# motor_driver_ver4_0.net
KiCad netlist of a schematic drawn in EAGLE
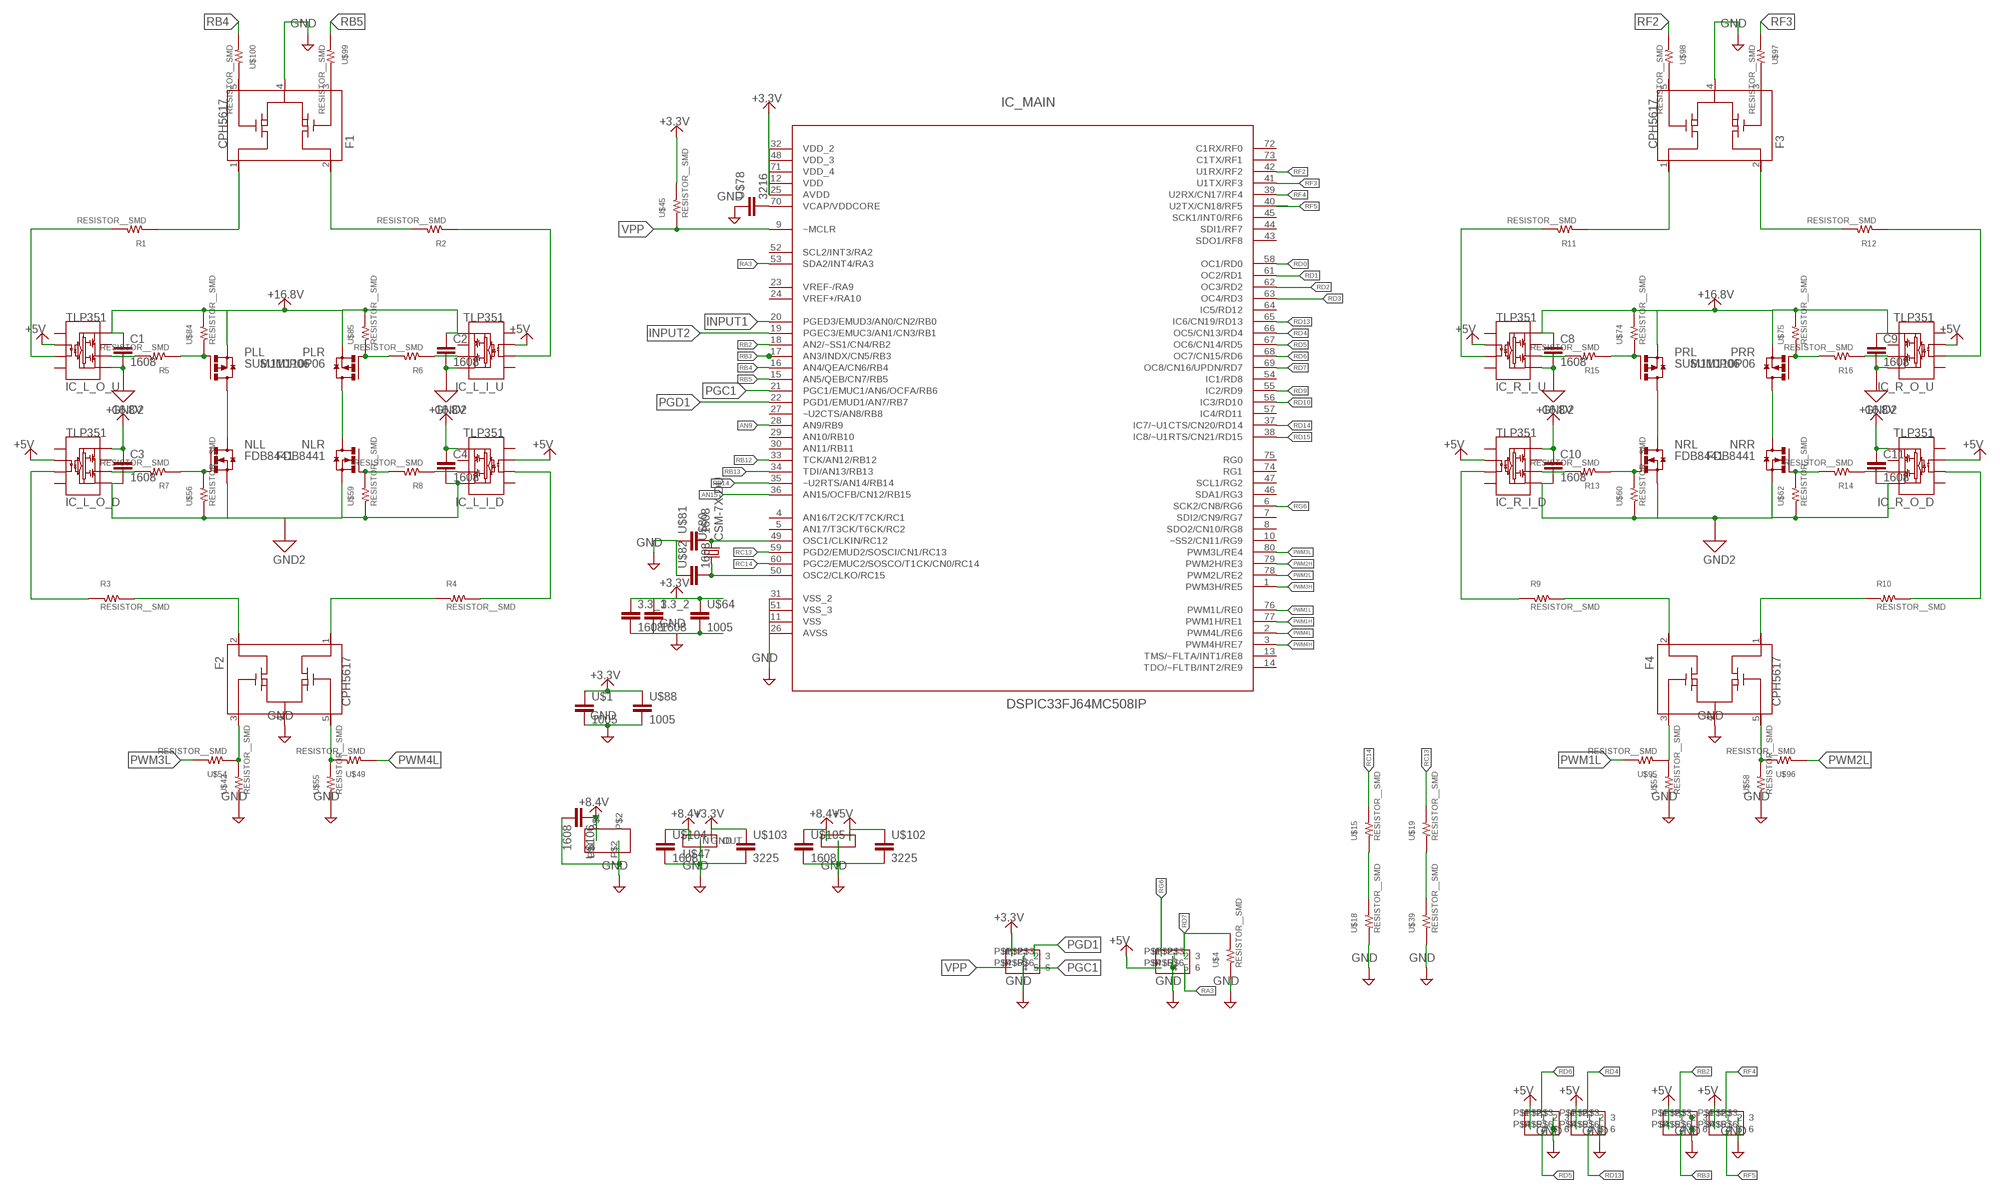
[diagram p0: schematic, sheet 1]

(export (version "E")
  (design (tool "Eeschema 10.0.6"))
  (components
    (comp (ref "3.3_1")
      (value "1608")
      (footprint "eagle-import:1608")
      (libsource (lib "eagle-import") (part "1608"))
    )
    (comp (ref "3.3_2")
      (value "1608")
      (footprint "eagle-import:1608")
      (libsource (lib "eagle-import") (part "1608"))
    )
    (comp (ref "C1")
      (value "1608")
      (footprint "eagle-import:1608")
      (libsource (lib "eagle-import") (part "1608"))
    )
    (comp (ref "C2")
      (value "1608")
      (footprint "eagle-import:1608")
      (libsource (lib "eagle-import") (part "1608"))
    )
    (comp (ref "C3")
      (value "1608")
      (footprint "eagle-import:1608")
      (libsource (lib "eagle-import") (part "1608"))
    )
    (comp (ref "C4")
      (value "1608")
      (footprint "eagle-import:1608")
      (libsource (lib "eagle-import") (part "1608"))
    )
    (comp (ref "C8")
      (value "1608")
      (footprint "eagle-import:1608")
      (libsource (lib "eagle-import") (part "1608"))
    )
    (comp (ref "C9")
      (value "1608")
      (footprint "eagle-import:1608")
      (libsource (lib "eagle-import") (part "1608"))
    )
    (comp (ref "C10")
      (value "1608")
      (footprint "eagle-import:1608")
      (libsource (lib "eagle-import") (part "1608"))
    )
    (comp (ref "C11")
      (value "1608")
      (footprint "eagle-import:1608")
      (libsource (lib "eagle-import") (part "1608"))
    )
    (comp (ref "F1")
      (value "CPH5617")
      (footprint "eagle-import:CHP-5")
      (libsource (lib "eagle-import") (part "CPH5617"))
    )
    (comp (ref "F2")
      (value "CPH5617")
      (footprint "eagle-import:CHP-5")
      (libsource (lib "eagle-import") (part "CPH5617"))
    )
    (comp (ref "F3")
      (value "CPH5617")
      (footprint "eagle-import:CHP-5")
      (libsource (lib "eagle-import") (part "CPH5617"))
    )
    (comp (ref "F4")
      (value "CPH5617")
      (footprint "eagle-import:CHP-5")
      (libsource (lib "eagle-import") (part "CPH5617"))
    )
    (comp (ref "IC_L_I_D")
      (value "TLP351")
      (footprint "eagle-import:DIL08")
      (libsource (lib "eagle-import") (part "TLP351"))
    )
    (comp (ref "IC_L_I_U")
      (value "TLP351")
      (footprint "eagle-import:DIL08")
      (libsource (lib "eagle-import") (part "TLP351"))
    )
    (comp (ref "IC_L_O_D")
      (value "TLP351")
      (footprint "eagle-import:DIL08")
      (libsource (lib "eagle-import") (part "TLP351"))
    )
    (comp (ref "IC_L_O_U")
      (value "TLP351")
      (footprint "eagle-import:DIL08")
      (libsource (lib "eagle-import") (part "TLP351"))
    )
    (comp (ref "IC_MAIN")
      (value "DSPIC33FJ64MC508IP")
      (footprint "eagle-import:QFP50P1400X1400X120-80N")
      (libsource (lib "eagle-import") (part "DSPIC33FJ64MC508IP"))
    )
    (comp (ref "IC_R_I_D")
      (value "TLP351")
      (footprint "eagle-import:DIL08")
      (libsource (lib "eagle-import") (part "TLP351"))
    )
    (comp (ref "IC_R_I_U")
      (value "TLP351")
      (footprint "eagle-import:DIL08")
      (libsource (lib "eagle-import") (part "TLP351"))
    )
    (comp (ref "IC_R_O_D")
      (value "TLP351")
      (footprint "eagle-import:DIL08")
      (libsource (lib "eagle-import") (part "TLP351"))
    )
    (comp (ref "IC_R_O_U")
      (value "TLP351")
      (footprint "eagle-import:DIL08")
      (libsource (lib "eagle-import") (part "TLP351"))
    )
    (comp (ref "NLL")
      (value "FDB8441")
      (footprint "eagle-import:TO-263")
      (libsource (lib "eagle-import") (part "FDB8441"))
    )
    (comp (ref "NLR")
      (value "FDB8441")
      (footprint "eagle-import:TO-263")
      (libsource (lib "eagle-import") (part "FDB8441"))
    )
    (comp (ref "NRL")
      (value "FDB8441")
      (footprint "eagle-import:TO-263")
      (libsource (lib "eagle-import") (part "FDB8441"))
    )
    (comp (ref "NRR")
      (value "FDB8441")
      (footprint "eagle-import:TO-263")
      (libsource (lib "eagle-import") (part "FDB8441"))
    )
    (comp (ref "PLL")
      (value "SUM110P06")
      (footprint "eagle-import:TO-263")
      (libsource (lib "eagle-import") (part "SUM110P06"))
    )
    (comp (ref "PLR")
      (value "SUM110P06")
      (footprint "eagle-import:TO-263")
      (libsource (lib "eagle-import") (part "SUM110P06"))
    )
    (comp (ref "PRL")
      (value "SUM110P06")
      (footprint "eagle-import:TO-263")
      (libsource (lib "eagle-import") (part "SUM110P06"))
    )
    (comp (ref "PRR")
      (value "SUM110P06")
      (footprint "eagle-import:TO-263")
      (libsource (lib "eagle-import") (part "SUM110P06"))
    )
    (comp (ref "R1")
      (value "RESISTOR__SMD")
      (footprint "eagle-import:1608")
      (libsource (lib "eagle-import") (part "RESISTOR__SMD"))
    )
    (comp (ref "R2")
      (value "RESISTOR__SMD")
      (footprint "eagle-import:1608")
      (libsource (lib "eagle-import") (part "RESISTOR__SMD"))
    )
    (comp (ref "R3")
      (value "RESISTOR__SMD")
      (footprint "eagle-import:1608")
      (libsource (lib "eagle-import") (part "RESISTOR__SMD"))
    )
    (comp (ref "R4")
      (value "RESISTOR__SMD")
      (footprint "eagle-import:1608")
      (libsource (lib "eagle-import") (part "RESISTOR__SMD"))
    )
    (comp (ref "R5")
      (value "RESISTOR__SMD")
      (footprint "eagle-import:1608")
      (libsource (lib "eagle-import") (part "RESISTOR__SMD"))
    )
    (comp (ref "R6")
      (value "RESISTOR__SMD")
      (footprint "eagle-import:1608")
      (libsource (lib "eagle-import") (part "RESISTOR__SMD"))
    )
    (comp (ref "R7")
      (value "RESISTOR__SMD")
      (footprint "eagle-import:1608")
      (libsource (lib "eagle-import") (part "RESISTOR__SMD"))
    )
    (comp (ref "R8")
      (value "RESISTOR__SMD")
      (footprint "eagle-import:1608")
      (libsource (lib "eagle-import") (part "RESISTOR__SMD"))
    )
    (comp (ref "R9")
      (value "RESISTOR__SMD")
      (footprint "eagle-import:1608")
      (libsource (lib "eagle-import") (part "RESISTOR__SMD"))
    )
    (comp (ref "R10")
      (value "RESISTOR__SMD")
      (footprint "eagle-import:1608")
      (libsource (lib "eagle-import") (part "RESISTOR__SMD"))
    )
    (comp (ref "R11")
      (value "RESISTOR__SMD")
      (footprint "eagle-import:1608")
      (libsource (lib "eagle-import") (part "RESISTOR__SMD"))
    )
    (comp (ref "R12")
      (value "RESISTOR__SMD")
      (footprint "eagle-import:1608")
      (libsource (lib "eagle-import") (part "RESISTOR__SMD"))
    )
    (comp (ref "R13")
      (value "RESISTOR__SMD")
      (footprint "eagle-import:1608")
      (libsource (lib "eagle-import") (part "RESISTOR__SMD"))
    )
    (comp (ref "R14")
      (value "RESISTOR__SMD")
      (footprint "eagle-import:1608")
      (libsource (lib "eagle-import") (part "RESISTOR__SMD"))
    )
    (comp (ref "R15")
      (value "RESISTOR__SMD")
      (footprint "eagle-import:1608")
      (libsource (lib "eagle-import") (part "RESISTOR__SMD"))
    )
    (comp (ref "R16")
      (value "RESISTOR__SMD")
      (footprint "eagle-import:1608")
      (libsource (lib "eagle-import") (part "RESISTOR__SMD"))
    )
    (comp (ref "RA3")
      (value "PIN_HEADER_32")
      (footprint "eagle-import:PIN_HEADER_3_2")
      (libsource (lib "eagle-import") (part "PIN_HEADER_32"))
    )
    (comp (ref "U$1")
      (value "1005")
      (footprint "eagle-import:1005")
      (libsource (lib "eagle-import") (part "1005"))
    )
    (comp (ref "U$4")
      (value "RESISTOR__SMD")
      (footprint "eagle-import:1608")
      (libsource (lib "eagle-import") (part "RESISTOR__SMD"))
    )
    (comp (ref "U$5")
      (value "PIN_HEADER_32")
      (footprint "eagle-import:PIN_HEADER_3_2")
      (libsource (lib "eagle-import") (part "PIN_HEADER_32"))
    )
    (comp (ref "U$15")
      (value "RESISTOR__SMD")
      (footprint "eagle-import:1608")
      (libsource (lib "eagle-import") (part "RESISTOR__SMD"))
    )
    (comp (ref "U$18")
      (value "RESISTOR__SMD")
      (footprint "eagle-import:1608")
      (libsource (lib "eagle-import") (part "RESISTOR__SMD"))
    )
    (comp (ref "U$19")
      (value "RESISTOR__SMD")
      (footprint "eagle-import:1608")
      (libsource (lib "eagle-import") (part "RESISTOR__SMD"))
    )
    (comp (ref "U$20")
      (value "PIN_HEADER_32")
      (footprint "eagle-import:PIN_HEADER_3_2")
      (libsource (lib "eagle-import") (part "PIN_HEADER_32"))
    )
    (comp (ref "U$39")
      (value "RESISTOR__SMD")
      (footprint "eagle-import:1608")
      (libsource (lib "eagle-import") (part "RESISTOR__SMD"))
    )
    (comp (ref "U$42")
      (value "RESISTOR__SMD")
      (footprint "eagle-import:1608")
      (libsource (lib "eagle-import") (part "RESISTOR__SMD"))
    )
    (comp (ref "U$45")
      (value "RESISTOR__SMD")
      (footprint "eagle-import:1608")
      (libsource (lib "eagle-import") (part "RESISTOR__SMD"))
    )
    (comp (ref "U$47")
      (value "TA48M033F")
      (footprint "eagle-import:ＴＡ４８")
      (libsource (lib "eagle-import") (part "TA48M033F"))
    )
    (comp (ref "U$49")
      (value "RESISTOR__SMD")
      (footprint "eagle-import:1608")
      (libsource (lib "eagle-import") (part "RESISTOR__SMD"))
    )
    (comp (ref "U$51")
      (value "PIN_HEADER_2")
      (footprint "eagle-import:PIN_HEADER_2S")
      (libsource (lib "eagle-import") (part "PIN_HEADER_2"))
    )
    (comp (ref "U$54")
      (value "RESISTOR__SMD")
      (footprint "eagle-import:1608")
      (libsource (lib "eagle-import") (part "RESISTOR__SMD"))
    )
    (comp (ref "U$55")
      (value "RESISTOR__SMD")
      (footprint "eagle-import:1608")
      (libsource (lib "eagle-import") (part "RESISTOR__SMD"))
    )
    (comp (ref "U$56")
      (value "RESISTOR__SMD")
      (footprint "eagle-import:1608")
      (libsource (lib "eagle-import") (part "RESISTOR__SMD"))
    )
    (comp (ref "U$57")
      (value "RESISTOR__SMD")
      (footprint "eagle-import:1608")
      (libsource (lib "eagle-import") (part "RESISTOR__SMD"))
    )
    (comp (ref "U$58")
      (value "RESISTOR__SMD")
      (footprint "eagle-import:1608")
      (libsource (lib "eagle-import") (part "RESISTOR__SMD"))
    )
    (comp (ref "U$59")
      (value "RESISTOR__SMD")
      (footprint "eagle-import:1608")
      (libsource (lib "eagle-import") (part "RESISTOR__SMD"))
    )
    (comp (ref "U$60")
      (value "RESISTOR__SMD")
      (footprint "eagle-import:1608")
      (libsource (lib "eagle-import") (part "RESISTOR__SMD"))
    )
    (comp (ref "U$62")
      (value "RESISTOR__SMD")
      (footprint "eagle-import:1608")
      (libsource (lib "eagle-import") (part "RESISTOR__SMD"))
    )
    (comp (ref "U$64")
      (value "1005")
      (footprint "eagle-import:1005")
      (libsource (lib "eagle-import") (part "1005"))
    )
    (comp (ref "U$65")
      (value "TA48M05F")
      (footprint "eagle-import:ＴＡ４８")
      (libsource (lib "eagle-import") (part "TA48M05F"))
    )
    (comp (ref "U$66")
      (value "PIN_HEADER_32")
      (footprint "eagle-import:PIN_HEADER_3_2")
      (libsource (lib "eagle-import") (part "PIN_HEADER_32"))
    )
    (comp (ref "U$67")
      (value "PIN_HEADER_32")
      (footprint "eagle-import:PIN_HEADER_3_2")
      (libsource (lib "eagle-import") (part "PIN_HEADER_32"))
    )
    (comp (ref "U$74")
      (value "RESISTOR__SMD")
      (footprint "eagle-import:1608")
      (libsource (lib "eagle-import") (part "RESISTOR__SMD"))
    )
    (comp (ref "U$75")
      (value "RESISTOR__SMD")
      (footprint "eagle-import:1608")
      (libsource (lib "eagle-import") (part "RESISTOR__SMD"))
    )
    (comp (ref "U$78")
      (value "3216")
      (footprint "eagle-import:3216")
      (libsource (lib "eagle-import") (part "3216"))
    )
    (comp (ref "U$80")
      (value "CSM-7X-DU")
      (footprint "eagle-import:CSM-7X-DU")
      (libsource (lib "eagle-import") (part "CSM-7X-DU"))
    )
    (comp (ref "U$81")
      (value "1608")
      (footprint "eagle-import:1608")
      (libsource (lib "eagle-import") (part "1608"))
    )
    (comp (ref "U$82")
      (value "1608")
      (footprint "eagle-import:1608")
      (libsource (lib "eagle-import") (part "1608"))
    )
    (comp (ref "U$84")
      (value "RESISTOR__SMD")
      (footprint "eagle-import:1608")
      (libsource (lib "eagle-import") (part "RESISTOR__SMD"))
    )
    (comp (ref "U$85")
      (value "RESISTOR__SMD")
      (footprint "eagle-import:1608")
      (libsource (lib "eagle-import") (part "RESISTOR__SMD"))
    )
    (comp (ref "U$86")
      (value "PIN_HEADER_32")
      (footprint "eagle-import:PIN_HEADER_3_2")
      (libsource (lib "eagle-import") (part "PIN_HEADER_32"))
    )
    (comp (ref "U$88")
      (value "1005")
      (footprint "eagle-import:1005")
      (libsource (lib "eagle-import") (part "1005"))
    )
    (comp (ref "U$95")
      (value "RESISTOR__SMD")
      (footprint "eagle-import:1608")
      (libsource (lib "eagle-import") (part "RESISTOR__SMD"))
    )
    (comp (ref "U$96")
      (value "RESISTOR__SMD")
      (footprint "eagle-import:1608")
      (libsource (lib "eagle-import") (part "RESISTOR__SMD"))
    )
    (comp (ref "U$97")
      (value "RESISTOR__SMD")
      (footprint "eagle-import:1608")
      (libsource (lib "eagle-import") (part "RESISTOR__SMD"))
    )
    (comp (ref "U$98")
      (value "RESISTOR__SMD")
      (footprint "eagle-import:1608")
      (libsource (lib "eagle-import") (part "RESISTOR__SMD"))
    )
    (comp (ref "U$99")
      (value "RESISTOR__SMD")
      (footprint "eagle-import:1608")
      (libsource (lib "eagle-import") (part "RESISTOR__SMD"))
    )
    (comp (ref "U$100")
      (value "RESISTOR__SMD")
      (footprint "eagle-import:1608")
      (libsource (lib "eagle-import") (part "RESISTOR__SMD"))
    )
    (comp (ref "U$102")
      (value "3225")
      (footprint "eagle-import:3225")
      (libsource (lib "eagle-import") (part "3225"))
    )
    (comp (ref "U$103")
      (value "3225")
      (footprint "eagle-import:3225")
      (libsource (lib "eagle-import") (part "3225"))
    )
    (comp (ref "U$104")
      (value "1608")
      (footprint "eagle-import:1608")
      (libsource (lib "eagle-import") (part "1608"))
    )
    (comp (ref "U$105")
      (value "1608")
      (footprint "eagle-import:1608")
      (libsource (lib "eagle-import") (part "1608"))
    )
    (comp (ref "U$106")
      (value "1608")
      (footprint "eagle-import:1608")
      (libsource (lib "eagle-import") (part "1608"))
    )
  )
  (nets
    (net (code "1") (name "+3.3V") (class "Default")
      (node (ref "3.3_1") (pin "P$1") (pinfunction "1_P$1") (pintype "passive"))
      (node (ref "3.3_2") (pin "P$1") (pinfunction "1_P$1") (pintype "passive"))
      (node (ref "IC_MAIN") (pin "12") (pinfunction "VDD_12") (pintype "power_in"))
      (node (ref "IC_MAIN") (pin "25") (pinfunction "AVDD_25") (pintype "power_in"))
      (node (ref "IC_MAIN") (pin "32") (pinfunction "VDD_2_32") (pintype "power_in"))
      (node (ref "IC_MAIN") (pin "48") (pinfunction "VDD_3_48") (pintype "power_in"))
      (node (ref "IC_MAIN") (pin "71") (pinfunction "VDD_4_71") (pintype "power_in"))
      (node (ref "U$1") (pin "1") (pinfunction "1_1") (pintype "passive"))
      (node (ref "U$103") (pin "P$1") (pinfunction "1_P$1") (pintype "passive"))
      (node (ref "U$45") (pin "2") (pinfunction "P$2_2") (pintype "passive"))
      (node (ref "U$47") (pin "3") (pinfunction "OUT_3") (pintype "bidirectional"))
      (node (ref "U$64") (pin "1") (pinfunction "1_1") (pintype "passive"))
      (node (ref "U$86") (pin "P$1") (pinfunction "1_P$1") (pintype "bidirectional"))
      (node (ref "U$88") (pin "1") (pinfunction "1_1") (pintype "passive"))
    )
    (net (code "2") (name "+5V") (class "Default")
      (node (ref "IC_L_I_D") (pin "2") (pinfunction "LED+_2") (pintype "bidirectional"))
      (node (ref "IC_L_I_U") (pin "2") (pinfunction "LED+_2") (pintype "bidirectional"))
      (node (ref "IC_L_O_D") (pin "2") (pinfunction "LED+_2") (pintype "bidirectional"))
      (node (ref "IC_L_O_U") (pin "2") (pinfunction "LED+_2") (pintype "bidirectional"))
      (node (ref "IC_R_I_D") (pin "2") (pinfunction "LED+_2") (pintype "bidirectional"))
      (node (ref "IC_R_I_U") (pin "2") (pinfunction "LED+_2") (pintype "bidirectional"))
      (node (ref "IC_R_O_D") (pin "2") (pinfunction "LED+_2") (pintype "bidirectional"))
      (node (ref "IC_R_O_U") (pin "2") (pinfunction "LED+_2") (pintype "bidirectional"))
      (node (ref "RA3") (pin "P$4") (pinfunction "4_P$4") (pintype "bidirectional"))
      (node (ref "U$102") (pin "P$1") (pinfunction "1_P$1") (pintype "passive"))
      (node (ref "U$20") (pin "P$1") (pinfunction "1_P$1") (pintype "bidirectional"))
      (node (ref "U$20") (pin "P$4") (pinfunction "4_P$4") (pintype "bidirectional"))
      (node (ref "U$5") (pin "P$1") (pinfunction "1_P$1") (pintype "bidirectional"))
      (node (ref "U$5") (pin "P$4") (pinfunction "4_P$4") (pintype "bidirectional"))
      (node (ref "U$65") (pin "3") (pinfunction "OUT_3") (pintype "bidirectional"))
      (node (ref "U$66") (pin "P$1") (pinfunction "1_P$1") (pintype "bidirectional"))
      (node (ref "U$66") (pin "P$4") (pinfunction "4_P$4") (pintype "bidirectional"))
      (node (ref "U$67") (pin "P$1") (pinfunction "1_P$1") (pintype "bidirectional"))
      (node (ref "U$67") (pin "P$4") (pinfunction "4_P$4") (pintype "bidirectional"))
    )
    (net (code "3") (name "+8.4V") (class "Default")
      (node (ref "U$104") (pin "P$1") (pinfunction "1_P$1") (pintype "passive"))
      (node (ref "U$105") (pin "P$1") (pinfunction "1_P$1") (pintype "passive"))
      (node (ref "U$106") (pin "P$1") (pinfunction "1_P$1") (pintype "passive"))
      (node (ref "U$47") (pin "1") (pinfunction "IN_1") (pintype "bidirectional"))
      (node (ref "U$51") (pin "P$1") (pinfunction "P$1_P$1") (pintype "bidirectional"))
      (node (ref "U$65") (pin "1") (pinfunction "IN_1") (pintype "bidirectional"))
    )
    (net (code "4") (name "+16.8V") (class "Default")
      (node (ref "C1") (pin "P$1") (pinfunction "1_P$1") (pintype "passive"))
      (node (ref "C10") (pin "P$1") (pinfunction "1_P$1") (pintype "passive"))
      (node (ref "C11") (pin "P$1") (pinfunction "1_P$1") (pintype "passive"))
      (node (ref "C2") (pin "P$1") (pinfunction "1_P$1") (pintype "passive"))
      (node (ref "C3") (pin "P$1") (pinfunction "1_P$1") (pintype "passive"))
      (node (ref "C4") (pin "P$1") (pinfunction "1_P$1") (pintype "passive"))
      (node (ref "C8") (pin "P$1") (pinfunction "1_P$1") (pintype "passive"))
      (node (ref "C9") (pin "P$1") (pinfunction "1_P$1") (pintype "passive"))
      (node (ref "IC_L_I_D") (pin "8") (pinfunction "VDD_8") (pintype "bidirectional"))
      (node (ref "IC_L_I_U") (pin "8") (pinfunction "VDD_8") (pintype "bidirectional"))
      (node (ref "IC_L_O_D") (pin "8") (pinfunction "VDD_8") (pintype "bidirectional"))
      (node (ref "IC_L_O_U") (pin "8") (pinfunction "VDD_8") (pintype "bidirectional"))
      (node (ref "IC_R_I_D") (pin "8") (pinfunction "VDD_8") (pintype "bidirectional"))
      (node (ref "IC_R_I_U") (pin "8") (pinfunction "VDD_8") (pintype "bidirectional"))
      (node (ref "IC_R_O_D") (pin "8") (pinfunction "VDD_8") (pintype "bidirectional"))
      (node (ref "IC_R_O_U") (pin "8") (pinfunction "VDD_8") (pintype "bidirectional"))
      (node (ref "PLL") (pin "2") (pinfunction "S_2") (pintype "passive"))
      (node (ref "PLR") (pin "2") (pinfunction "S_2") (pintype "passive"))
      (node (ref "PRL") (pin "2") (pinfunction "S_2") (pintype "passive"))
      (node (ref "PRR") (pin "2") (pinfunction "S_2") (pintype "passive"))
      (node (ref "U$74") (pin "2") (pinfunction "P$2_2") (pintype "passive"))
      (node (ref "U$75") (pin "2") (pinfunction "P$2_2") (pintype "passive"))
      (node (ref "U$84") (pin "2") (pinfunction "P$2_2") (pintype "passive"))
      (node (ref "U$85") (pin "2") (pinfunction "P$2_2") (pintype "passive"))
    )
    (net (code "5") (name "AN9") (class "Default")
      (node (ref "IC_MAIN") (pin "28") (pinfunction "AN9/RB9_28") (pintype "bidirectional"))
    )
    (net (code "6") (name "AN15") (class "Default")
      (node (ref "IC_MAIN") (pin "36") (pinfunction "AN15/OCFB/CN12/RB15_36") (pintype "bidirectional"))
    )
    (net (code "7") (name "GND") (class "Default")
      (node (ref "3.3_1") (pin "P$2") (pinfunction "2_P$2") (pintype "passive"))
      (node (ref "3.3_2") (pin "P$2") (pinfunction "2_P$2") (pintype "passive"))
      (node (ref "F1") (pin "4") (pinfunction "S_4") (pintype "bidirectional"))
      (node (ref "F2") (pin "4") (pinfunction "S_4") (pintype "bidirectional"))
      (node (ref "F3") (pin "4") (pinfunction "S_4") (pintype "bidirectional"))
      (node (ref "F4") (pin "4") (pinfunction "S_4") (pintype "bidirectional"))
      (node (ref "IC_MAIN") (pin "11") (pinfunction "VSS_11") (pintype "power_in"))
      (node (ref "IC_MAIN") (pin "26") (pinfunction "AVSS_26") (pintype "power_in"))
      (node (ref "IC_MAIN") (pin "31") (pinfunction "VSS_2_31") (pintype "power_in"))
      (node (ref "IC_MAIN") (pin "51") (pinfunction "VSS_3_51") (pintype "power_in"))
      (node (ref "RA3") (pin "P$2") (pinfunction "2_P$2") (pintype "bidirectional"))
      (node (ref "RA3") (pin "P$5") (pinfunction "5_P$5") (pintype "bidirectional"))
      (node (ref "U$1") (pin "2") (pinfunction "2_2") (pintype "passive"))
      (node (ref "U$102") (pin "P$2") (pinfunction "2_P$2") (pintype "passive"))
      (node (ref "U$103") (pin "P$2") (pinfunction "2_P$2") (pintype "passive"))
      (node (ref "U$104") (pin "P$2") (pinfunction "2_P$2") (pintype "passive"))
      (node (ref "U$105") (pin "P$2") (pinfunction "2_P$2") (pintype "passive"))
      (node (ref "U$106") (pin "P$2") (pinfunction "2_P$2") (pintype "passive"))
      (node (ref "U$18") (pin "1") (pinfunction "P$1_1") (pintype "passive"))
      (node (ref "U$20") (pin "P$3") (pinfunction "3_P$3") (pintype "bidirectional"))
      (node (ref "U$20") (pin "P$6") (pinfunction "6_P$6") (pintype "bidirectional"))
      (node (ref "U$39") (pin "1") (pinfunction "P$1_1") (pintype "passive"))
      (node (ref "U$4") (pin "1") (pinfunction "P$1_1") (pintype "passive"))
      (node (ref "U$42") (pin "1") (pinfunction "P$1_1") (pintype "passive"))
      (node (ref "U$47") (pin "2") (pinfunction "GND_2") (pintype "bidirectional"))
      (node (ref "U$5") (pin "P$3") (pinfunction "3_P$3") (pintype "bidirectional"))
      (node (ref "U$5") (pin "P$6") (pinfunction "6_P$6") (pintype "bidirectional"))
      (node (ref "U$51") (pin "P$2") (pinfunction "P$2_P$2") (pintype "bidirectional"))
      (node (ref "U$55") (pin "1") (pinfunction "P$1_1") (pintype "passive"))
      (node (ref "U$57") (pin "1") (pinfunction "P$1_1") (pintype "passive"))
      (node (ref "U$58") (pin "1") (pinfunction "P$1_1") (pintype "passive"))
      (node (ref "U$64") (pin "2") (pinfunction "2_2") (pintype "passive"))
      (node (ref "U$65") (pin "2") (pinfunction "GND_2") (pintype "bidirectional"))
      (node (ref "U$66") (pin "P$3") (pinfunction "3_P$3") (pintype "bidirectional"))
      (node (ref "U$66") (pin "P$6") (pinfunction "6_P$6") (pintype "bidirectional"))
      (node (ref "U$67") (pin "P$3") (pinfunction "3_P$3") (pintype "bidirectional"))
      (node (ref "U$67") (pin "P$6") (pinfunction "6_P$6") (pintype "bidirectional"))
      (node (ref "U$78") (pin "P$1") (pinfunction "1_P$1") (pintype "passive"))
      (node (ref "U$81") (pin "P$1") (pinfunction "1_P$1") (pintype "passive"))
      (node (ref "U$82") (pin "P$1") (pinfunction "1_P$1") (pintype "passive"))
      (node (ref "U$86") (pin "P$2") (pinfunction "2_P$2") (pintype "bidirectional"))
      (node (ref "U$86") (pin "P$5") (pinfunction "5_P$5") (pintype "bidirectional"))
      (node (ref "U$88") (pin "2") (pinfunction "2_2") (pintype "passive"))
    )
    (net (code "8") (name "GND2") (class "Default")
      (node (ref "C1") (pin "P$2") (pinfunction "2_P$2") (pintype "passive"))
      (node (ref "C10") (pin "P$2") (pinfunction "2_P$2") (pintype "passive"))
      (node (ref "C11") (pin "P$2") (pinfunction "2_P$2") (pintype "passive"))
      (node (ref "C2") (pin "P$2") (pinfunction "2_P$2") (pintype "passive"))
      (node (ref "C3") (pin "P$2") (pinfunction "2_P$2") (pintype "passive"))
      (node (ref "C4") (pin "P$2") (pinfunction "2_P$2") (pintype "passive"))
      (node (ref "C8") (pin "P$2") (pinfunction "2_P$2") (pintype "passive"))
      (node (ref "C9") (pin "P$2") (pinfunction "2_P$2") (pintype "passive"))
      (node (ref "IC_L_I_D") (pin "5") (pinfunction "GND_5") (pintype "bidirectional"))
      (node (ref "IC_L_I_U") (pin "5") (pinfunction "GND_5") (pintype "bidirectional"))
      (node (ref "IC_L_O_D") (pin "5") (pinfunction "GND_5") (pintype "bidirectional"))
      (node (ref "IC_L_O_U") (pin "5") (pinfunction "GND_5") (pintype "bidirectional"))
      (node (ref "IC_R_I_D") (pin "5") (pinfunction "GND_5") (pintype "bidirectional"))
      (node (ref "IC_R_I_U") (pin "5") (pinfunction "GND_5") (pintype "bidirectional"))
      (node (ref "IC_R_O_D") (pin "5") (pinfunction "GND_5") (pintype "bidirectional"))
      (node (ref "IC_R_O_U") (pin "5") (pinfunction "GND_5") (pintype "bidirectional"))
      (node (ref "NLL") (pin "2") (pinfunction "S_2") (pintype "passive"))
      (node (ref "NLR") (pin "2") (pinfunction "S_2") (pintype "passive"))
      (node (ref "NRL") (pin "2") (pinfunction "S_2") (pintype "passive"))
      (node (ref "NRR") (pin "2") (pinfunction "S_2") (pintype "passive"))
      (node (ref "U$56") (pin "1") (pinfunction "P$1_1") (pintype "passive"))
      (node (ref "U$59") (pin "1") (pinfunction "P$1_1") (pintype "passive"))
      (node (ref "U$60") (pin "1") (pinfunction "P$1_1") (pintype "passive"))
      (node (ref "U$62") (pin "1") (pinfunction "P$1_1") (pintype "passive"))
    )
    (net (code "9") (name "INPUT1") (class "Default")
      (node (ref "IC_MAIN") (pin "20") (pinfunction "PGED3/EMUD3/AN0/CN2/RB0_20") (pintype "bidirectional"))
    )
    (net (code "10") (name "INPUT2") (class "Default")
      (node (ref "IC_MAIN") (pin "19") (pinfunction "PGEC3/EMUC3/AN1/CN3/RB1_19") (pintype "bidirectional"))
    )
    (net (code "11") (name "Net-(F1-D1)") (class "Default")
      (node (ref "F1") (pin "1") (pinfunction "D1_1") (pintype "bidirectional"))
      (node (ref "R1") (pin "1") (pinfunction "P$1_1") (pintype "passive"))
    )
    (net (code "12") (name "Net-(F1-D2)") (class "Default")
      (node (ref "F1") (pin "2") (pinfunction "D2_2") (pintype "bidirectional"))
      (node (ref "R2") (pin "2") (pinfunction "P$2_2") (pintype "passive"))
    )
    (net (code "13") (name "Net-(F1-G1)") (class "Default")
      (node (ref "F1") (pin "5") (pinfunction "G1_5") (pintype "bidirectional"))
      (node (ref "U$100") (pin "2") (pinfunction "P$2_2") (pintype "passive"))
    )
    (net (code "14") (name "Net-(F1-G2)") (class "Default")
      (node (ref "F1") (pin "3") (pinfunction "G2_3") (pintype "bidirectional"))
      (node (ref "U$99") (pin "2") (pinfunction "P$2_2") (pintype "passive"))
    )
    (net (code "15") (name "Net-(F2-D1)") (class "Default")
      (node (ref "F2") (pin "1") (pinfunction "D1_1") (pintype "bidirectional"))
      (node (ref "R4") (pin "1") (pinfunction "P$1_1") (pintype "passive"))
    )
    (net (code "16") (name "Net-(F2-D2)") (class "Default")
      (node (ref "F2") (pin "2") (pinfunction "D2_2") (pintype "bidirectional"))
      (node (ref "R3") (pin "2") (pinfunction "P$2_2") (pintype "passive"))
    )
    (net (code "17") (name "Net-(F2-G1)") (class "Default")
      (node (ref "F2") (pin "5") (pinfunction "G1_5") (pintype "bidirectional"))
      (node (ref "U$49") (pin "2") (pinfunction "P$2_2") (pintype "passive"))
      (node (ref "U$55") (pin "2") (pinfunction "P$2_2") (pintype "passive"))
    )
    (net (code "18") (name "Net-(F2-G2)") (class "Default")
      (node (ref "F2") (pin "3") (pinfunction "G2_3") (pintype "bidirectional"))
      (node (ref "U$42") (pin "2") (pinfunction "P$2_2") (pintype "passive"))
      (node (ref "U$54") (pin "1") (pinfunction "P$1_1") (pintype "passive"))
    )
    (net (code "19") (name "Net-(F3-D1)") (class "Default")
      (node (ref "F3") (pin "1") (pinfunction "D1_1") (pintype "bidirectional"))
      (node (ref "R11") (pin "1") (pinfunction "P$1_1") (pintype "passive"))
    )
    (net (code "20") (name "Net-(F3-D2)") (class "Default")
      (node (ref "F3") (pin "2") (pinfunction "D2_2") (pintype "bidirectional"))
      (node (ref "R12") (pin "2") (pinfunction "P$2_2") (pintype "passive"))
    )
    (net (code "21") (name "Net-(F3-G1)") (class "Default")
      (node (ref "F3") (pin "5") (pinfunction "G1_5") (pintype "bidirectional"))
      (node (ref "U$98") (pin "2") (pinfunction "P$2_2") (pintype "passive"))
    )
    (net (code "22") (name "Net-(F3-G2)") (class "Default")
      (node (ref "F3") (pin "3") (pinfunction "G2_3") (pintype "bidirectional"))
      (node (ref "U$97") (pin "2") (pinfunction "P$2_2") (pintype "passive"))
    )
    (net (code "23") (name "Net-(F4-D1)") (class "Default")
      (node (ref "F4") (pin "1") (pinfunction "D1_1") (pintype "bidirectional"))
      (node (ref "R10") (pin "1") (pinfunction "P$1_1") (pintype "passive"))
    )
    (net (code "24") (name "Net-(F4-D2)") (class "Default")
      (node (ref "F4") (pin "2") (pinfunction "D2_2") (pintype "bidirectional"))
      (node (ref "R9") (pin "2") (pinfunction "P$2_2") (pintype "passive"))
    )
    (net (code "25") (name "Net-(F4-G1)") (class "Default")
      (node (ref "F4") (pin "5") (pinfunction "G1_5") (pintype "bidirectional"))
      (node (ref "U$58") (pin "2") (pinfunction "P$2_2") (pintype "passive"))
      (node (ref "U$96") (pin "2") (pinfunction "P$2_2") (pintype "passive"))
    )
    (net (code "26") (name "Net-(F4-G2)") (class "Default")
      (node (ref "F4") (pin "3") (pinfunction "G2_3") (pintype "bidirectional"))
      (node (ref "U$57") (pin "2") (pinfunction "P$2_2") (pintype "passive"))
      (node (ref "U$95") (pin "1") (pinfunction "P$1_1") (pintype "passive"))
    )
    (net (code "27") (name "Net-(IC_L_I_D-LED-)") (class "Default")
      (node (ref "IC_L_I_D") (pin "3") (pinfunction "LED-_3") (pintype "bidirectional"))
      (node (ref "R4") (pin "2") (pinfunction "P$2_2") (pintype "passive"))
    )
    (net (code "28") (name "Net-(IC_L_I_D-OUT)") (class "Default")
      (node (ref "IC_L_I_D") (pin "6") (pinfunction "OUT_6") (pintype "output"))
      (node (ref "R8") (pin "1") (pinfunction "P$1_1") (pintype "passive"))
    )
    (net (code "29") (name "Net-(IC_L_I_U-LED-)") (class "Default")
      (node (ref "IC_L_I_U") (pin "3") (pinfunction "LED-_3") (pintype "bidirectional"))
      (node (ref "R2") (pin "1") (pinfunction "P$1_1") (pintype "passive"))
    )
    (net (code "30") (name "Net-(IC_L_I_U-OUT)") (class "Default")
      (node (ref "IC_L_I_U") (pin "6") (pinfunction "OUT_6") (pintype "output"))
      (node (ref "R6") (pin "1") (pinfunction "P$1_1") (pintype "passive"))
    )
    (net (code "31") (name "Net-(IC_L_O_D-LED-)") (class "Default")
      (node (ref "IC_L_O_D") (pin "3") (pinfunction "LED-_3") (pintype "bidirectional"))
      (node (ref "R3") (pin "1") (pinfunction "P$1_1") (pintype "passive"))
    )
    (net (code "32") (name "Net-(IC_L_O_D-OUT)") (class "Default")
      (node (ref "IC_L_O_D") (pin "6") (pinfunction "OUT_6") (pintype "output"))
      (node (ref "R7") (pin "2") (pinfunction "P$2_2") (pintype "passive"))
    )
    (net (code "33") (name "Net-(IC_L_O_U-LED-)") (class "Default")
      (node (ref "IC_L_O_U") (pin "3") (pinfunction "LED-_3") (pintype "bidirectional"))
      (node (ref "R1") (pin "2") (pinfunction "P$2_2") (pintype "passive"))
    )
    (net (code "34") (name "Net-(IC_L_O_U-OUT)") (class "Default")
      (node (ref "IC_L_O_U") (pin "6") (pinfunction "OUT_6") (pintype "output"))
      (node (ref "R5") (pin "2") (pinfunction "P$2_2") (pintype "passive"))
    )
    (net (code "35") (name "Net-(IC_MAIN-OSC1{slash}CLKIN{slash}RC12)") (class "Default")
      (node (ref "IC_MAIN") (pin "49") (pinfunction "OSC1/CLKIN/RC12_49") (pintype "bidirectional"))
      (node (ref "U$80") (pin "2") (pinfunction "2_2") (pintype "passive"))
      (node (ref "U$81") (pin "P$2") (pinfunction "2_P$2") (pintype "passive"))
    )
    (net (code "36") (name "Net-(IC_MAIN-OSC2{slash}CLKO{slash}RC15)") (class "Default")
      (node (ref "IC_MAIN") (pin "50") (pinfunction "OSC2/CLKO/RC15_50") (pintype "bidirectional"))
      (node (ref "U$80") (pin "1") (pinfunction "1_1") (pintype "passive"))
      (node (ref "U$82") (pin "P$2") (pinfunction "2_P$2") (pintype "passive"))
    )
    (net (code "37") (name "Net-(IC_MAIN-VCAP{slash}VDDCORE)") (class "Default")
      (node (ref "IC_MAIN") (pin "70") (pinfunction "VCAP/VDDCORE_70") (pintype "power_in"))
      (node (ref "U$78") (pin "P$2") (pinfunction "2_P$2") (pintype "passive"))
    )
    (net (code "38") (name "Net-(IC_R_I_D-LED-)") (class "Default")
      (node (ref "IC_R_I_D") (pin "3") (pinfunction "LED-_3") (pintype "bidirectional"))
      (node (ref "R9") (pin "1") (pinfunction "P$1_1") (pintype "passive"))
    )
    (net (code "39") (name "Net-(IC_R_I_D-OUT)") (class "Default")
      (node (ref "IC_R_I_D") (pin "6") (pinfunction "OUT_6") (pintype "output"))
      (node (ref "R13") (pin "2") (pinfunction "P$2_2") (pintype "passive"))
    )
    (net (code "40") (name "Net-(IC_R_I_U-LED-)") (class "Default")
      (node (ref "IC_R_I_U") (pin "3") (pinfunction "LED-_3") (pintype "bidirectional"))
      (node (ref "R11") (pin "2") (pinfunction "P$2_2") (pintype "passive"))
    )
    (net (code "41") (name "Net-(IC_R_I_U-OUT)") (class "Default")
      (node (ref "IC_R_I_U") (pin "6") (pinfunction "OUT_6") (pintype "output"))
      (node (ref "R15") (pin "2") (pinfunction "P$2_2") (pintype "passive"))
    )
    (net (code "42") (name "Net-(IC_R_O_D-LED-)") (class "Default")
      (node (ref "IC_R_O_D") (pin "3") (pinfunction "LED-_3") (pintype "bidirectional"))
      (node (ref "R10") (pin "2") (pinfunction "P$2_2") (pintype "passive"))
    )
    (net (code "43") (name "Net-(IC_R_O_D-OUT)") (class "Default")
      (node (ref "IC_R_O_D") (pin "6") (pinfunction "OUT_6") (pintype "output"))
      (node (ref "R14") (pin "1") (pinfunction "P$1_1") (pintype "passive"))
    )
    (net (code "44") (name "Net-(IC_R_O_U-LED-)") (class "Default")
      (node (ref "IC_R_O_U") (pin "3") (pinfunction "LED-_3") (pintype "bidirectional"))
      (node (ref "R12") (pin "1") (pinfunction "P$1_1") (pintype "passive"))
    )
    (net (code "45") (name "Net-(IC_R_O_U-OUT)") (class "Default")
      (node (ref "IC_R_O_U") (pin "6") (pinfunction "OUT_6") (pintype "output"))
      (node (ref "R16") (pin "1") (pinfunction "P$1_1") (pintype "passive"))
    )
    (net (code "46") (name "Net-(NLL-D)") (class "Default")
      (node (ref "NLL") (pin "3") (pinfunction "D_3") (pintype "passive"))
      (node (ref "PLL") (pin "3") (pinfunction "D_3") (pintype "passive"))
    )
    (net (code "47") (name "Net-(NLL-G)") (class "Default")
      (node (ref "NLL") (pin "1") (pinfunction "G_1") (pintype "passive"))
      (node (ref "R7") (pin "1") (pinfunction "P$1_1") (pintype "passive"))
      (node (ref "U$56") (pin "2") (pinfunction "P$2_2") (pintype "passive"))
    )
    (net (code "48") (name "Net-(NLR-D)") (class "Default")
      (node (ref "NLR") (pin "3") (pinfunction "D_3") (pintype "passive"))
      (node (ref "PLR") (pin "3") (pinfunction "D_3") (pintype "passive"))
    )
    (net (code "49") (name "Net-(NLR-G)") (class "Default")
      (node (ref "NLR") (pin "1") (pinfunction "G_1") (pintype "passive"))
      (node (ref "R8") (pin "2") (pinfunction "P$2_2") (pintype "passive"))
      (node (ref "U$59") (pin "2") (pinfunction "P$2_2") (pintype "passive"))
    )
    (net (code "50") (name "Net-(NRL-D)") (class "Default")
      (node (ref "NRL") (pin "3") (pinfunction "D_3") (pintype "passive"))
      (node (ref "PRL") (pin "3") (pinfunction "D_3") (pintype "passive"))
    )
    (net (code "51") (name "Net-(NRL-G)") (class "Default")
      (node (ref "NRL") (pin "1") (pinfunction "G_1") (pintype "passive"))
      (node (ref "R13") (pin "1") (pinfunction "P$1_1") (pintype "passive"))
      (node (ref "U$60") (pin "2") (pinfunction "P$2_2") (pintype "passive"))
    )
    (net (code "52") (name "Net-(NRR-D)") (class "Default")
      (node (ref "NRR") (pin "3") (pinfunction "D_3") (pintype "passive"))
      (node (ref "PRR") (pin "3") (pinfunction "D_3") (pintype "passive"))
    )
    (net (code "53") (name "Net-(NRR-G)") (class "Default")
      (node (ref "NRR") (pin "1") (pinfunction "G_1") (pintype "passive"))
      (node (ref "R14") (pin "2") (pinfunction "P$2_2") (pintype "passive"))
      (node (ref "U$62") (pin "2") (pinfunction "P$2_2") (pintype "passive"))
    )
    (net (code "54") (name "Net-(PLL-G)") (class "Default")
      (node (ref "PLL") (pin "1") (pinfunction "G_1") (pintype "passive"))
      (node (ref "R5") (pin "1") (pinfunction "P$1_1") (pintype "passive"))
      (node (ref "U$84") (pin "1") (pinfunction "P$1_1") (pintype "passive"))
    )
    (net (code "55") (name "Net-(PLR-G)") (class "Default")
      (node (ref "PLR") (pin "1") (pinfunction "G_1") (pintype "passive"))
      (node (ref "R6") (pin "2") (pinfunction "P$2_2") (pintype "passive"))
      (node (ref "U$85") (pin "1") (pinfunction "P$1_1") (pintype "passive"))
    )
    (net (code "56") (name "Net-(PRL-G)") (class "Default")
      (node (ref "PRL") (pin "1") (pinfunction "G_1") (pintype "passive"))
      (node (ref "R15") (pin "1") (pinfunction "P$1_1") (pintype "passive"))
      (node (ref "U$74") (pin "1") (pinfunction "P$1_1") (pintype "passive"))
    )
    (net (code "57") (name "Net-(PRR-G)") (class "Default")
      (node (ref "PRR") (pin "1") (pinfunction "G_1") (pintype "passive"))
      (node (ref "R16") (pin "2") (pinfunction "P$2_2") (pintype "passive"))
      (node (ref "U$75") (pin "1") (pinfunction "P$1_1") (pintype "passive"))
    )
    (net (code "58") (name "Net-(U$15-P$1)") (class "Default")
      (node (ref "U$15") (pin "1") (pinfunction "P$1_1") (pintype "passive"))
      (node (ref "U$18") (pin "2") (pinfunction "P$2_2") (pintype "passive"))
    )
    (net (code "59") (name "Net-(U$19-P$1)") (class "Default")
      (node (ref "U$19") (pin "1") (pinfunction "P$1_1") (pintype "passive"))
      (node (ref "U$39") (pin "2") (pinfunction "P$2_2") (pintype "passive"))
    )
    (net (code "60") (name "PGC1") (class "Default")
      (node (ref "IC_MAIN") (pin "21") (pinfunction "PGC1/EMUC1/AN6/OCFA/RB6_21") (pintype "bidirectional"))
      (node (ref "U$86") (pin "P$6") (pinfunction "6_P$6") (pintype "bidirectional"))
    )
    (net (code "61") (name "PGD1") (class "Default")
      (node (ref "IC_MAIN") (pin "22") (pinfunction "PGD1/EMUD1/AN7/RB7_22") (pintype "bidirectional"))
      (node (ref "U$86") (pin "P$3") (pinfunction "3_P$3") (pintype "bidirectional"))
    )
    (net (code "62") (name "PWM1H") (class "Default")
      (node (ref "IC_MAIN") (pin "77") (pinfunction "PWM1H/RE1_77") (pintype "bidirectional"))
    )
    (net (code "63") (name "PWM1L") (class "Default")
      (node (ref "IC_MAIN") (pin "76") (pinfunction "PWM1L/RE0_76") (pintype "bidirectional"))
      (node (ref "U$95") (pin "2") (pinfunction "P$2_2") (pintype "passive"))
    )
    (net (code "64") (name "PWM2H") (class "Default")
      (node (ref "IC_MAIN") (pin "79") (pinfunction "PWM2H/RE3_79") (pintype "bidirectional"))
    )
    (net (code "65") (name "PWM2L") (class "Default")
      (node (ref "IC_MAIN") (pin "78") (pinfunction "PWM2L/RE2_78") (pintype "bidirectional"))
      (node (ref "U$96") (pin "1") (pinfunction "P$1_1") (pintype "passive"))
    )
    (net (code "66") (name "PWM3H") (class "Default")
      (node (ref "IC_MAIN") (pin "1") (pinfunction "PWM3H/RE5_1") (pintype "bidirectional"))
    )
    (net (code "67") (name "PWM3L") (class "Default")
      (node (ref "IC_MAIN") (pin "80") (pinfunction "PWM3L/RE4_80") (pintype "bidirectional"))
      (node (ref "U$54") (pin "2") (pinfunction "P$2_2") (pintype "passive"))
    )
    (net (code "68") (name "PWM4H") (class "Default")
      (node (ref "IC_MAIN") (pin "3") (pinfunction "PWM4H/RE7_3") (pintype "bidirectional"))
    )
    (net (code "69") (name "PWM4L") (class "Default")
      (node (ref "IC_MAIN") (pin "2") (pinfunction "PWM4L/RE6_2") (pintype "bidirectional"))
      (node (ref "U$49") (pin "1") (pinfunction "P$1_1") (pintype "passive"))
    )
    (net (code "70") (name "RA3") (class "Default")
      (node (ref "IC_MAIN") (pin "53") (pinfunction "SDA2/INT4/RA3_53") (pintype "bidirectional"))
      (node (ref "RA3") (pin "P$6") (pinfunction "6_P$6") (pintype "bidirectional"))
    )
    (net (code "71") (name "RB2") (class "Default")
      (node (ref "IC_MAIN") (pin "18") (pinfunction "AN2/~{SS1/CN4/RB2}_18") (pintype "bidirectional"))
      (node (ref "U$5") (pin "P$2") (pinfunction "2_P$2") (pintype "bidirectional"))
    )
    (net (code "72") (name "RB3") (class "Default")
      (node (ref "IC_MAIN") (pin "17") (pinfunction "AN3/INDX/CN5/RB3_17") (pintype "bidirectional"))
      (node (ref "U$5") (pin "P$5") (pinfunction "5_P$5") (pintype "bidirectional"))
    )
    (net (code "73") (name "RB4") (class "Default")
      (node (ref "IC_MAIN") (pin "16") (pinfunction "AN4/QEA/CN6/RB4_16") (pintype "bidirectional"))
      (node (ref "U$100") (pin "1") (pinfunction "P$1_1") (pintype "passive"))
    )
    (net (code "74") (name "RB5") (class "Default")
      (node (ref "IC_MAIN") (pin "15") (pinfunction "AN5/QEB/CN7/RB5_15") (pintype "bidirectional"))
      (node (ref "U$99") (pin "1") (pinfunction "P$1_1") (pintype "passive"))
    )
    (net (code "75") (name "RB12") (class "Default")
      (node (ref "IC_MAIN") (pin "33") (pinfunction "TCK/AN12/RB12_33") (pintype "bidirectional"))
    )
    (net (code "76") (name "RB13") (class "Default")
      (node (ref "IC_MAIN") (pin "34") (pinfunction "TDI/AN13/RB13_34") (pintype "bidirectional"))
    )
    (net (code "77") (name "RB14") (class "Default")
      (node (ref "IC_MAIN") (pin "35") (pinfunction "~{U2RTS/AN14/RB14}_35") (pintype "bidirectional"))
    )
    (net (code "78") (name "RC13") (class "Default")
      (node (ref "IC_MAIN") (pin "59") (pinfunction "PGD2/EMUD2/SOSCI/CN1/RC13_59") (pintype "bidirectional"))
      (node (ref "U$19") (pin "2") (pinfunction "P$2_2") (pintype "passive"))
    )
    (net (code "79") (name "RC14") (class "Default")
      (node (ref "IC_MAIN") (pin "60") (pinfunction "PGC2/EMUC2/SOSCO/T1CK/CN0/RC14_60") (pintype "bidirectional"))
      (node (ref "U$15") (pin "2") (pinfunction "P$2_2") (pintype "passive"))
    )
    (net (code "80") (name "RD0") (class "Default")
      (node (ref "IC_MAIN") (pin "58") (pinfunction "OC1/RD0_58") (pintype "bidirectional"))
    )
    (net (code "81") (name "RD1") (class "Default")
      (node (ref "IC_MAIN") (pin "61") (pinfunction "OC2/RD1_61") (pintype "bidirectional"))
    )
    (net (code "82") (name "RD2") (class "Default")
      (node (ref "IC_MAIN") (pin "62") (pinfunction "OC3/RD2_62") (pintype "bidirectional"))
    )
    (net (code "83") (name "RD3") (class "Default")
      (node (ref "IC_MAIN") (pin "63") (pinfunction "OC4/RD3_63") (pintype "bidirectional"))
    )
    (net (code "84") (name "RD4") (class "Default")
      (node (ref "IC_MAIN") (pin "66") (pinfunction "OC5/CN13/RD4_66") (pintype "bidirectional"))
      (node (ref "U$67") (pin "P$2") (pinfunction "2_P$2") (pintype "bidirectional"))
    )
    (net (code "85") (name "RD5") (class "Default")
      (node (ref "IC_MAIN") (pin "67") (pinfunction "OC6/CN14/RD5_67") (pintype "bidirectional"))
      (node (ref "U$66") (pin "P$5") (pinfunction "5_P$5") (pintype "bidirectional"))
    )
    (net (code "86") (name "RD6") (class "Default")
      (node (ref "IC_MAIN") (pin "68") (pinfunction "OC7/CN15/RD6_68") (pintype "bidirectional"))
      (node (ref "U$66") (pin "P$2") (pinfunction "2_P$2") (pintype "bidirectional"))
    )
    (net (code "87") (name "RD7") (class "Default")
      (node (ref "IC_MAIN") (pin "69") (pinfunction "OC8/CN16/UPDN/RD7_69") (pintype "bidirectional"))
      (node (ref "RA3") (pin "P$3") (pinfunction "3_P$3") (pintype "bidirectional"))
      (node (ref "U$4") (pin "2") (pinfunction "P$2_2") (pintype "passive"))
    )
    (net (code "88") (name "RD9") (class "Default")
      (node (ref "IC_MAIN") (pin "55") (pinfunction "IC2/RD9_55") (pintype "bidirectional"))
    )
    (net (code "89") (name "RD10") (class "Default")
      (node (ref "IC_MAIN") (pin "56") (pinfunction "IC3/RD10_56") (pintype "bidirectional"))
    )
    (net (code "90") (name "RD13") (class "Default")
      (node (ref "IC_MAIN") (pin "65") (pinfunction "IC6/CN19/RD13_65") (pintype "bidirectional"))
      (node (ref "U$67") (pin "P$5") (pinfunction "5_P$5") (pintype "bidirectional"))
    )
    (net (code "91") (name "RD14") (class "Default")
      (node (ref "IC_MAIN") (pin "37") (pinfunction "IC7/~{U1CTS/CN20/RD14}_37") (pintype "bidirectional"))
    )
    (net (code "92") (name "RD15") (class "Default")
      (node (ref "IC_MAIN") (pin "38") (pinfunction "IC8/~{U1RTS/CN21/RD15}_38") (pintype "bidirectional"))
    )
    (net (code "93") (name "RF2") (class "Default")
      (node (ref "IC_MAIN") (pin "42") (pinfunction "U1RX/RF2_42") (pintype "bidirectional"))
      (node (ref "U$98") (pin "1") (pinfunction "P$1_1") (pintype "passive"))
    )
    (net (code "94") (name "RF3") (class "Default")
      (node (ref "IC_MAIN") (pin "41") (pinfunction "U1TX/RF3_41") (pintype "bidirectional"))
      (node (ref "U$97") (pin "1") (pinfunction "P$1_1") (pintype "passive"))
    )
    (net (code "95") (name "RF4") (class "Default")
      (node (ref "IC_MAIN") (pin "39") (pinfunction "U2RX/CN17/RF4_39") (pintype "bidirectional"))
      (node (ref "U$20") (pin "P$2") (pinfunction "2_P$2") (pintype "bidirectional"))
    )
    (net (code "96") (name "RF5") (class "Default")
      (node (ref "IC_MAIN") (pin "40") (pinfunction "U2TX/CN18/RF5_40") (pintype "bidirectional"))
      (node (ref "U$20") (pin "P$5") (pinfunction "5_P$5") (pintype "bidirectional"))
    )
    (net (code "97") (name "RG6") (class "Default")
      (node (ref "IC_MAIN") (pin "6") (pinfunction "SCK2/CN8/RG6_6") (pintype "bidirectional"))
      (node (ref "RA3") (pin "P$1") (pinfunction "1_P$1") (pintype "bidirectional"))
    )
    (net (code "98") (name "VPP") (class "Default")
      (node (ref "IC_MAIN") (pin "9") (pinfunction "~{MCLR}_9") (pintype "input"))
      (node (ref "U$45") (pin "1") (pinfunction "P$1_1") (pintype "passive"))
      (node (ref "U$86") (pin "P$4") (pinfunction "4_P$4") (pintype "bidirectional"))
    )
    (net (code "99") (name "unconnected-(IC_L_I_D-NC1-Pad1)") (class "Default")
      (node (ref "IC_L_I_D") (pin "1") (pinfunction "NC1_1") (pintype "no_connect"))
    )
    (net (code "100") (name "unconnected-(IC_L_I_D-NC4-Pad4)") (class "Default")
      (node (ref "IC_L_I_D") (pin "4") (pinfunction "NC4_4") (pintype "no_connect"))
    )
    (net (code "101") (name "unconnected-(IC_L_I_D-NC7-Pad7)") (class "Default")
      (node (ref "IC_L_I_D") (pin "7") (pinfunction "NC7_7") (pintype "no_connect"))
    )
    (net (code "102") (name "unconnected-(IC_L_I_U-NC1-Pad1)") (class "Default")
      (node (ref "IC_L_I_U") (pin "1") (pinfunction "NC1_1") (pintype "no_connect"))
    )
    (net (code "103") (name "unconnected-(IC_L_I_U-NC4-Pad4)") (class "Default")
      (node (ref "IC_L_I_U") (pin "4") (pinfunction "NC4_4") (pintype "no_connect"))
    )
    (net (code "104") (name "unconnected-(IC_L_I_U-NC7-Pad7)") (class "Default")
      (node (ref "IC_L_I_U") (pin "7") (pinfunction "NC7_7") (pintype "no_connect"))
    )
    (net (code "105") (name "unconnected-(IC_L_O_D-NC1-Pad1)") (class "Default")
      (node (ref "IC_L_O_D") (pin "1") (pinfunction "NC1_1") (pintype "no_connect"))
    )
    (net (code "106") (name "unconnected-(IC_L_O_D-NC4-Pad4)") (class "Default")
      (node (ref "IC_L_O_D") (pin "4") (pinfunction "NC4_4") (pintype "no_connect"))
    )
    (net (code "107") (name "unconnected-(IC_L_O_D-NC7-Pad7)") (class "Default")
      (node (ref "IC_L_O_D") (pin "7") (pinfunction "NC7_7") (pintype "no_connect"))
    )
    (net (code "108") (name "unconnected-(IC_L_O_U-NC1-Pad1)") (class "Default")
      (node (ref "IC_L_O_U") (pin "1") (pinfunction "NC1_1") (pintype "no_connect"))
    )
    (net (code "109") (name "unconnected-(IC_L_O_U-NC4-Pad4)") (class "Default")
      (node (ref "IC_L_O_U") (pin "4") (pinfunction "NC4_4") (pintype "no_connect"))
    )
    (net (code "110") (name "unconnected-(IC_L_O_U-NC7-Pad7)") (class "Default")
      (node (ref "IC_L_O_U") (pin "7") (pinfunction "NC7_7") (pintype "no_connect"))
    )
    (net (code "111") (name "unconnected-(IC_MAIN-AN10{slash}RB10-Pad29)") (class "Default")
      (node (ref "IC_MAIN") (pin "29") (pinfunction "AN10/RB10_29") (pintype "bidirectional"))
    )
    (net (code "112") (name "unconnected-(IC_MAIN-AN11{slash}RB11-Pad30)") (class "Default")
      (node (ref "IC_MAIN") (pin "30") (pinfunction "AN11/RB11_30") (pintype "bidirectional"))
    )
    (net (code "113") (name "unconnected-(IC_MAIN-AN16{slash}T2CK{slash}T7CK{slash}RC1-Pad4)") (class "Default")
      (node (ref "IC_MAIN") (pin "4") (pinfunction "AN16/T2CK/T7CK/RC1_4") (pintype "bidirectional"))
    )
    (net (code "114") (name "unconnected-(IC_MAIN-AN17{slash}T3CK{slash}T6CK{slash}RC2-Pad5)") (class "Default")
      (node (ref "IC_MAIN") (pin "5") (pinfunction "AN17/T3CK/T6CK/RC2_5") (pintype "bidirectional"))
    )
    (net (code "115") (name "unconnected-(IC_MAIN-C1RX{slash}RF0-Pad72)") (class "Default")
      (node (ref "IC_MAIN") (pin "72") (pinfunction "C1RX/RF0_72") (pintype "bidirectional"))
    )
    (net (code "116") (name "unconnected-(IC_MAIN-C1TX{slash}RF1-Pad73)") (class "Default")
      (node (ref "IC_MAIN") (pin "73") (pinfunction "C1TX/RF1_73") (pintype "bidirectional"))
    )
    (net (code "117") (name "unconnected-(IC_MAIN-IC1{slash}RD8-Pad54)") (class "Default")
      (node (ref "IC_MAIN") (pin "54") (pinfunction "IC1/RD8_54") (pintype "bidirectional"))
    )
    (net (code "118") (name "unconnected-(IC_MAIN-IC4{slash}RD11-Pad57)") (class "Default")
      (node (ref "IC_MAIN") (pin "57") (pinfunction "IC4/RD11_57") (pintype "bidirectional"))
    )
    (net (code "119") (name "unconnected-(IC_MAIN-IC5{slash}RD12-Pad64)") (class "Default")
      (node (ref "IC_MAIN") (pin "64") (pinfunction "IC5/RD12_64") (pintype "bidirectional"))
    )
    (net (code "120") (name "unconnected-(IC_MAIN-RG0-Pad75)") (class "Default")
      (node (ref "IC_MAIN") (pin "75") (pinfunction "RG0_75") (pintype "bidirectional"))
    )
    (net (code "121") (name "unconnected-(IC_MAIN-RG1-Pad74)") (class "Default")
      (node (ref "IC_MAIN") (pin "74") (pinfunction "RG1_74") (pintype "bidirectional"))
    )
    (net (code "122") (name "unconnected-(IC_MAIN-SCK1{slash}INT0{slash}RF6-Pad45)") (class "Default")
      (node (ref "IC_MAIN") (pin "45") (pinfunction "SCK1/INT0/RF6_45") (pintype "bidirectional"))
    )
    (net (code "123") (name "unconnected-(IC_MAIN-SCL1{slash}RG2-Pad47)") (class "Default")
      (node (ref "IC_MAIN") (pin "47") (pinfunction "SCL1/RG2_47") (pintype "bidirectional"))
    )
    (net (code "124") (name "unconnected-(IC_MAIN-SCL2{slash}INT3{slash}RA2-Pad52)") (class "Default")
      (node (ref "IC_MAIN") (pin "52") (pinfunction "SCL2/INT3/RA2_52") (pintype "bidirectional"))
    )
    (net (code "125") (name "unconnected-(IC_MAIN-SDA1{slash}RG3-Pad46)") (class "Default")
      (node (ref "IC_MAIN") (pin "46") (pinfunction "SDA1/RG3_46") (pintype "bidirectional"))
    )
    (net (code "126") (name "unconnected-(IC_MAIN-SDI1{slash}RF7-Pad44)") (class "Default")
      (node (ref "IC_MAIN") (pin "44") (pinfunction "SDI1/RF7_44") (pintype "bidirectional"))
    )
    (net (code "127") (name "unconnected-(IC_MAIN-SDI2{slash}CN9{slash}RG7-Pad7)") (class "Default")
      (node (ref "IC_MAIN") (pin "7") (pinfunction "SDI2/CN9/RG7_7") (pintype "bidirectional"))
    )
    (net (code "128") (name "unconnected-(IC_MAIN-SDO1{slash}RF8-Pad43)") (class "Default")
      (node (ref "IC_MAIN") (pin "43") (pinfunction "SDO1/RF8_43") (pintype "bidirectional"))
    )
    (net (code "129") (name "unconnected-(IC_MAIN-SDO2{slash}CN10{slash}RG8-Pad8)") (class "Default")
      (node (ref "IC_MAIN") (pin "8") (pinfunction "SDO2/CN10/RG8_8") (pintype "bidirectional"))
    )
    (net (code "130") (name "unconnected-(IC_MAIN-TDO{slash}~{FLTB{slash}INT2{slash}RE9}-Pad14)") (class "Default")
      (node (ref "IC_MAIN") (pin "14") (pinfunction "TDO/~{FLTB/INT2/RE9}_14") (pintype "bidirectional"))
    )
    (net (code "131") (name "unconnected-(IC_MAIN-TMS{slash}~{FLTA{slash}INT1{slash}RE8}-Pad13)") (class "Default")
      (node (ref "IC_MAIN") (pin "13") (pinfunction "TMS/~{FLTA/INT1/RE8}_13") (pintype "bidirectional"))
    )
    (net (code "132") (name "unconnected-(IC_MAIN-VREF+{slash}RA10-Pad24)") (class "Default")
      (node (ref "IC_MAIN") (pin "24") (pinfunction "VREF+/RA10_24") (pintype "bidirectional"))
    )
    (net (code "133") (name "unconnected-(IC_MAIN-VREF-{slash}RA9-Pad23)") (class "Default")
      (node (ref "IC_MAIN") (pin "23") (pinfunction "VREF-/RA9_23") (pintype "bidirectional"))
    )
    (net (code "134") (name "unconnected-(IC_MAIN-~{SS2{slash}CN11{slash}RG9}-Pad10)") (class "Default")
      (node (ref "IC_MAIN") (pin "10") (pinfunction "~{SS2/CN11/RG9}_10") (pintype "bidirectional"))
    )
    (net (code "135") (name "unconnected-(IC_MAIN-~{U2CTS{slash}AN8{slash}RB8}-Pad27)") (class "Default")
      (node (ref "IC_MAIN") (pin "27") (pinfunction "~{U2CTS/AN8/RB8}_27") (pintype "bidirectional"))
    )
    (net (code "136") (name "unconnected-(IC_R_I_D-NC1-Pad1)") (class "Default")
      (node (ref "IC_R_I_D") (pin "1") (pinfunction "NC1_1") (pintype "no_connect"))
    )
    (net (code "137") (name "unconnected-(IC_R_I_D-NC4-Pad4)") (class "Default")
      (node (ref "IC_R_I_D") (pin "4") (pinfunction "NC4_4") (pintype "no_connect"))
    )
    (net (code "138") (name "unconnected-(IC_R_I_D-NC7-Pad7)") (class "Default")
      (node (ref "IC_R_I_D") (pin "7") (pinfunction "NC7_7") (pintype "no_connect"))
    )
    (net (code "139") (name "unconnected-(IC_R_I_U-NC1-Pad1)") (class "Default")
      (node (ref "IC_R_I_U") (pin "1") (pinfunction "NC1_1") (pintype "no_connect"))
    )
    (net (code "140") (name "unconnected-(IC_R_I_U-NC4-Pad4)") (class "Default")
      (node (ref "IC_R_I_U") (pin "4") (pinfunction "NC4_4") (pintype "no_connect"))
    )
    (net (code "141") (name "unconnected-(IC_R_I_U-NC7-Pad7)") (class "Default")
      (node (ref "IC_R_I_U") (pin "7") (pinfunction "NC7_7") (pintype "no_connect"))
    )
    (net (code "142") (name "unconnected-(IC_R_O_D-NC1-Pad1)") (class "Default")
      (node (ref "IC_R_O_D") (pin "1") (pinfunction "NC1_1") (pintype "no_connect"))
    )
    (net (code "143") (name "unconnected-(IC_R_O_D-NC4-Pad4)") (class "Default")
      (node (ref "IC_R_O_D") (pin "4") (pinfunction "NC4_4") (pintype "no_connect"))
    )
    (net (code "144") (name "unconnected-(IC_R_O_D-NC7-Pad7)") (class "Default")
      (node (ref "IC_R_O_D") (pin "7") (pinfunction "NC7_7") (pintype "no_connect"))
    )
    (net (code "145") (name "unconnected-(IC_R_O_U-NC1-Pad1)") (class "Default")
      (node (ref "IC_R_O_U") (pin "1") (pinfunction "NC1_1") (pintype "no_connect"))
    )
    (net (code "146") (name "unconnected-(IC_R_O_U-NC4-Pad4)") (class "Default")
      (node (ref "IC_R_O_U") (pin "4") (pinfunction "NC4_4") (pintype "no_connect"))
    )
    (net (code "147") (name "unconnected-(IC_R_O_U-NC7-Pad7)") (class "Default")
      (node (ref "IC_R_O_U") (pin "7") (pinfunction "NC7_7") (pintype "no_connect"))
    )
  )
)
